# FLCOS_Projector_Driver.net
KiCad netlist of a schematic drawn in EAGLE
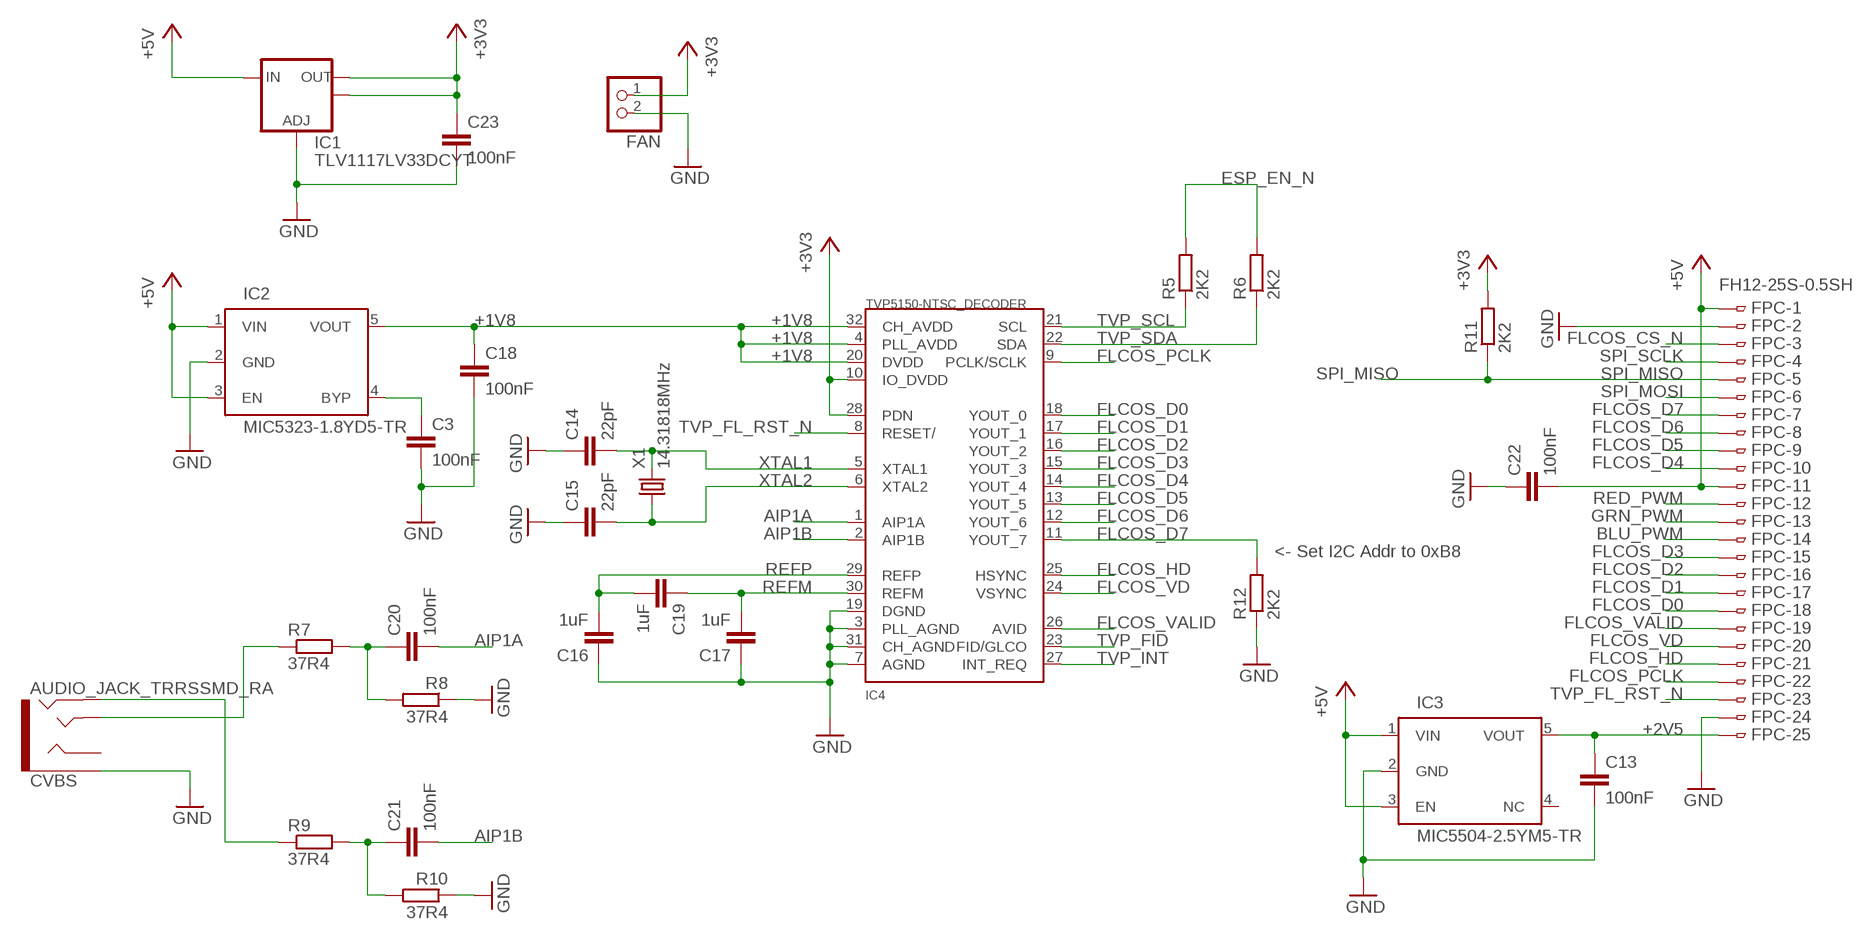
[diagram p0: schematic, sheet 1]
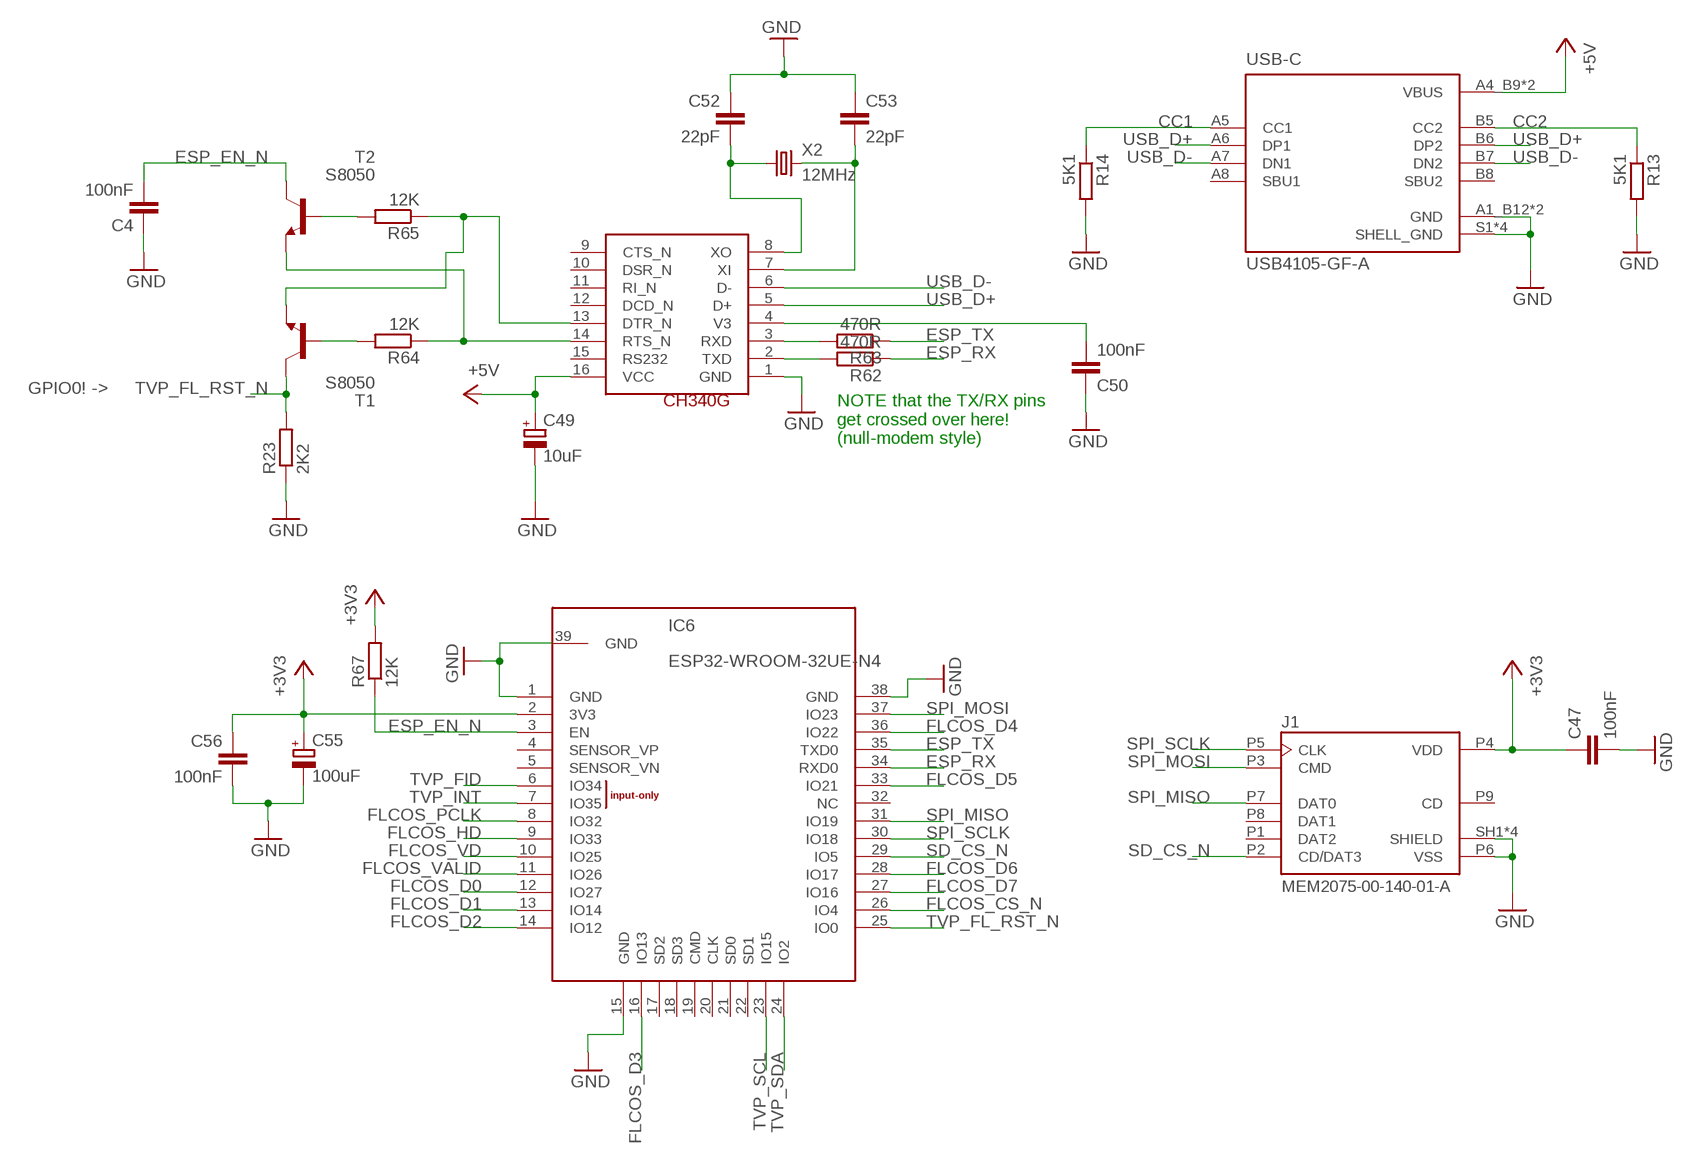
[diagram p1: schematic, sheet 2]
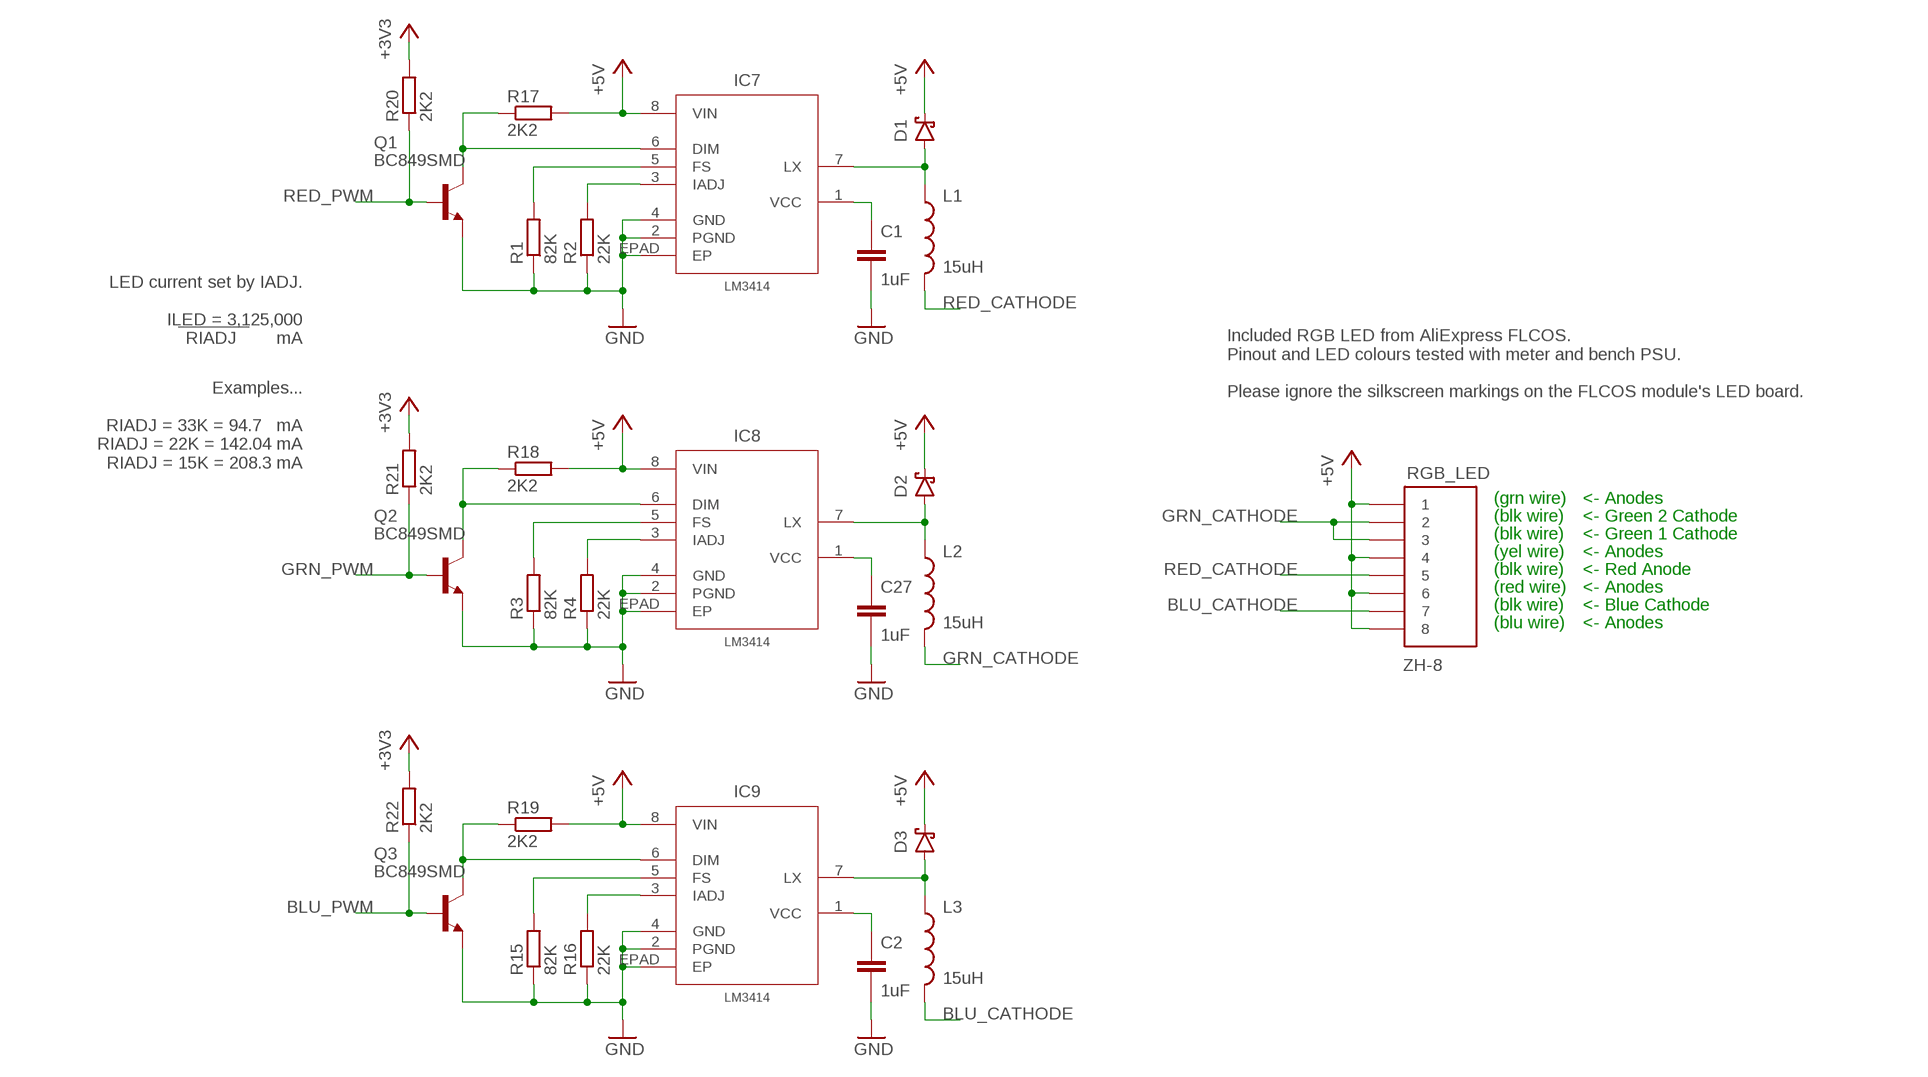
[diagram p2: schematic, sheet 3]

(export (version "E")
  (design (tool "Eeschema 10.0.6"))
  (components
    (comp (ref "C3")
      (value "100nF")
      (footprint "eagle-import:C0603")
      (libsource (lib "eagle-import") (part "C-EUC0603"))
    )
    (comp (ref "C13")
      (value "100nF")
      (footprint "eagle-import:C0603")
      (libsource (lib "eagle-import") (part "C-EUC0603"))
    )
    (comp (ref "C14")
      (value "22pF")
      (footprint "eagle-import:C0603")
      (libsource (lib "eagle-import") (part "C-EUC0603"))
    )
    (comp (ref "C15")
      (value "22pF")
      (footprint "eagle-import:C0603")
      (libsource (lib "eagle-import") (part "C-EUC0603"))
    )
    (comp (ref "C16")
      (value "1uF")
      (footprint "eagle-import:C0603")
      (libsource (lib "eagle-import") (part "C-EUC0603"))
    )
    (comp (ref "C17")
      (value "1uF")
      (footprint "eagle-import:C0603")
      (libsource (lib "eagle-import") (part "C-EUC0603"))
    )
    (comp (ref "C18")
      (value "100nF")
      (footprint "eagle-import:C0603")
      (libsource (lib "eagle-import") (part "C-EUC0603"))
    )
    (comp (ref "C19")
      (value "1uF")
      (footprint "eagle-import:C0603")
      (libsource (lib "eagle-import") (part "C-EUC0603"))
    )
    (comp (ref "C20")
      (value "100nF")
      (footprint "eagle-import:C0603")
      (libsource (lib "eagle-import") (part "C-EUC0603"))
    )
    (comp (ref "C21")
      (value "100nF")
      (footprint "eagle-import:C0603")
      (libsource (lib "eagle-import") (part "C-EUC0603"))
    )
    (comp (ref "C22")
      (value "100nF")
      (footprint "eagle-import:C0603")
      (libsource (lib "eagle-import") (part "C-EUC0603"))
    )
    (comp (ref "C23")
      (value "100nF")
      (footprint "eagle-import:C0603")
      (libsource (lib "eagle-import") (part "C-EUC0603"))
    )
    (comp (ref "CVBS")
      (value "AUDIO_JACK_TRRSSMD_RA")
      (footprint "eagle-import:AUDIO_JACK_3.5MM_TRRS_SMD_RA")
      (libsource (lib "eagle-import") (part "AUDIO_JACK_TRRSSMD_RA"))
    )
    (comp (ref "FAN")
      (value "JST_2PIN-THM")
      (footprint "eagle-import:JST-PH-2-THM")
      (libsource (lib "eagle-import") (part "JST_2PIN-THM"))
    )
    (comp (ref "FPC")
      (value "FH12-25S-0.5SH")
      (footprint "eagle-import:FH12-25S-0.5SH")
      (libsource (lib "eagle-import") (part "FH12-25S-0.5SH"))
    )
    (comp (ref "IC1")
      (value "TLV1117LV33DCYT")
      (footprint "eagle-import:SOT223")
      (libsource (lib "eagle-import") (part "V_REG_LM1117SOT223"))
    )
    (comp (ref "IC2")
      (value "MIC5323-1.8YD5-TR")
      (footprint "eagle-import:SOT23-5")
      (libsource (lib "eagle-import") (part "MIC5323-1.8YD5-TR"))
    )
    (comp (ref "IC3")
      (value "MIC5504-2.5YM5-TR")
      (footprint "eagle-import:SOT23-5")
      (libsource (lib "eagle-import") (part "MIC5504-2.5YM5-TR"))
    )
    (comp (ref "IC4")
      (value "TVP5150-NTSC_DECODER")
      (footprint "eagle-import:TQFP32-5MM")
      (libsource (lib "eagle-import") (part "TVP5150-NTSC_DECODER"))
    )
    (comp (ref "R5")
      (value "2K2")
      (footprint "eagle-import:R0603")
      (libsource (lib "eagle-import") (part "R-EU_R0603"))
    )
    (comp (ref "R6")
      (value "2K2")
      (footprint "eagle-import:R0603")
      (libsource (lib "eagle-import") (part "R-EU_R0603"))
    )
    (comp (ref "R7")
      (value "37R4")
      (footprint "eagle-import:R0603")
      (libsource (lib "eagle-import") (part "R-EU_R0603"))
    )
    (comp (ref "R8")
      (value "37R4")
      (footprint "eagle-import:R0603")
      (libsource (lib "eagle-import") (part "R-EU_R0603"))
    )
    (comp (ref "R9")
      (value "37R4")
      (footprint "eagle-import:R0603")
      (libsource (lib "eagle-import") (part "R-EU_R0603"))
    )
    (comp (ref "R10")
      (value "37R4")
      (footprint "eagle-import:R0603")
      (libsource (lib "eagle-import") (part "R-EU_R0603"))
    )
    (comp (ref "R11")
      (value "2K2")
      (footprint "eagle-import:R0603")
      (libsource (lib "eagle-import") (part "R-EU_R0603"))
    )
    (comp (ref "R12")
      (value "2K2")
      (footprint "eagle-import:R0603")
      (libsource (lib "eagle-import") (part "R-EU_R0603"))
    )
    (comp (ref "X1")
      (value "14.31818MHz")
      (footprint "eagle-import:CTS406")
      (libsource (lib "eagle-import") (part "CRYSTALCTS406"))
    )
    (comp (ref "C1")
      (value "1uF")
      (footprint "eagle-import:C0603")
      (libsource (lib "eagle-import") (part "CAPACITOR-CERAMICC0603"))
    )
    (comp (ref "C2")
      (value "1uF")
      (footprint "eagle-import:C0603")
      (libsource (lib "eagle-import") (part "CAPACITOR-CERAMICC0603"))
    )
    (comp (ref "C27")
      (value "1uF")
      (footprint "eagle-import:C0603")
      (libsource (lib "eagle-import") (part "CAPACITOR-CERAMICC0603"))
    )
    (comp (ref "D1")
      (value "\"SB34AFC-AU_R1_000A1 SB34AFC-AU_R1_000A1\"")
      (footprint "eagle-import:SMA-DIODE-SCHOTTKY")
      (libsource (lib "eagle-import") (part "DIODE-SCHOTTKYSMA"))
    )
    (comp (ref "D2")
      (value "\"SB34AFC-AU_R1_000A1 SB34AFC-AU_R1_000A1\"")
      (footprint "eagle-import:SMA-DIODE-SCHOTTKY")
      (libsource (lib "eagle-import") (part "DIODE-SCHOTTKYSMA"))
    )
    (comp (ref "D3")
      (value "\"SB34AFC-AU_R1_000A1 SB34AFC-AU_R1_000A1\"")
      (footprint "eagle-import:SMA-DIODE-SCHOTTKY")
      (libsource (lib "eagle-import") (part "DIODE-SCHOTTKYSMA"))
    )
    (comp (ref "IC7")
      (value "LM3414")
      (footprint "eagle-import:SO08-PAD")
      (libsource (lib "eagle-import") (part "LM3414SO08-PAD"))
    )
    (comp (ref "IC8")
      (value "LM3414")
      (footprint "eagle-import:SO08-PAD")
      (libsource (lib "eagle-import") (part "LM3414SO08-PAD"))
    )
    (comp (ref "IC9")
      (value "LM3414")
      (footprint "eagle-import:SO08-PAD")
      (libsource (lib "eagle-import") (part "LM3414SO08-PAD"))
    )
    (comp (ref "L1")
      (value "15uH")
      (footprint "eagle-import:TAIYO-YUDEN-6X6X2.8")
      (libsource (lib "eagle-import") (part "INDUCTOR-TAIYO-YUDEN-6X2.8"))
    )
    (comp (ref "L2")
      (value "15uH")
      (footprint "eagle-import:TAIYO-YUDEN-6X6X2.8")
      (libsource (lib "eagle-import") (part "INDUCTOR-TAIYO-YUDEN-6X2.8"))
    )
    (comp (ref "L3")
      (value "15uH")
      (footprint "eagle-import:TAIYO-YUDEN-6X6X2.8")
      (libsource (lib "eagle-import") (part "INDUCTOR-TAIYO-YUDEN-6X2.8"))
    )
    (comp (ref "Q1")
      (value "BC849SMD")
      (footprint "eagle-import:SOT23-BEC")
      (libsource (lib "eagle-import") (part "BC849SMD"))
    )
    (comp (ref "Q2")
      (value "BC849SMD")
      (footprint "eagle-import:SOT23-BEC")
      (libsource (lib "eagle-import") (part "BC849SMD"))
    )
    (comp (ref "Q3")
      (value "BC849SMD")
      (footprint "eagle-import:SOT23-BEC")
      (libsource (lib "eagle-import") (part "BC849SMD"))
    )
    (comp (ref "R1")
      (value "82K")
      (footprint "eagle-import:R0603")
      (libsource (lib "eagle-import") (part "R-EU_R0603"))
    )
    (comp (ref "R2")
      (value "22K")
      (footprint "eagle-import:R0603")
      (libsource (lib "eagle-import") (part "R-EU_R0603"))
    )
    (comp (ref "R3")
      (value "82K")
      (footprint "eagle-import:R0603")
      (libsource (lib "eagle-import") (part "R-EU_R0603"))
    )
    (comp (ref "R4")
      (value "22K")
      (footprint "eagle-import:R0603")
      (libsource (lib "eagle-import") (part "R-EU_R0603"))
    )
    (comp (ref "R15")
      (value "82K")
      (footprint "eagle-import:R0603")
      (libsource (lib "eagle-import") (part "R-EU_R0603"))
    )
    (comp (ref "R16")
      (value "22K")
      (footprint "eagle-import:R0603")
      (libsource (lib "eagle-import") (part "R-EU_R0603"))
    )
    (comp (ref "R17")
      (value "2K2")
      (footprint "eagle-import:R0603")
      (libsource (lib "eagle-import") (part "R-EU_R0603"))
    )
    (comp (ref "R18")
      (value "2K2")
      (footprint "eagle-import:R0603")
      (libsource (lib "eagle-import") (part "R-EU_R0603"))
    )
    (comp (ref "R19")
      (value "2K2")
      (footprint "eagle-import:R0603")
      (libsource (lib "eagle-import") (part "R-EU_R0603"))
    )
    (comp (ref "R20")
      (value "2K2")
      (footprint "eagle-import:R0603")
      (libsource (lib "eagle-import") (part "R-EU_R0603"))
    )
    (comp (ref "R21")
      (value "2K2")
      (footprint "eagle-import:R0603")
      (libsource (lib "eagle-import") (part "R-EU_R0603"))
    )
    (comp (ref "R22")
      (value "2K2")
      (footprint "eagle-import:R0603")
      (libsource (lib "eagle-import") (part "R-EU_R0603"))
    )
    (comp (ref "RGB_LED")
      (value "ZH-8")
      (footprint "eagle-import:ZH-8")
      (libsource (lib "eagle-import") (part "ZH-8"))
    )
    (comp (ref "C4")
      (value "100nF")
      (footprint "eagle-import:C0603")
      (libsource (lib "eagle-import") (part "C-EUC0603"))
    )
    (comp (ref "C47")
      (value "100nF")
      (footprint "eagle-import:C0603")
      (libsource (lib "eagle-import") (part "C-EUC0603"))
    )
    (comp (ref "C49")
      (value "10uF")
      (footprint "eagle-import:B_3528-21W")
      (libsource (lib "eagle-import") (part "CPOL-EUB/3528-21W"))
    )
    (comp (ref "C50")
      (value "100nF")
      (footprint "eagle-import:C0603")
      (libsource (lib "eagle-import") (part "C-EUC0603"))
    )
    (comp (ref "C52")
      (value "22pF")
      (footprint "eagle-import:C0603")
      (libsource (lib "eagle-import") (part "C-EUC0603"))
    )
    (comp (ref "C53")
      (value "22pF")
      (footprint "eagle-import:C0603")
      (libsource (lib "eagle-import") (part "C-EUC0603"))
    )
    (comp (ref "C55")
      (value "100uF")
      (footprint "eagle-import:C_6032-28R")
      (libsource (lib "eagle-import") (part "CPOL-EUC/6032-28R"))
    )
    (comp (ref "C56")
      (value "100nF")
      (footprint "eagle-import:C0603")
      (libsource (lib "eagle-import") (part "C-EUC0603"))
    )
    (comp (ref "IC5")
      (value "CH340G")
      (footprint "eagle-import:SOIC16")
      (libsource (lib "eagle-import") (part "CH340G"))
    )
    (comp (ref "IC6")
      (value "ESP32-WROOM-32UE-N4")
      (footprint "eagle-import:ESP32WROOM32D")
      (fields
        (field (name "MANUFACTURER_PART_NUMBER") "ESP32-WROOM-32U")
        (field (name "MOUSER_PART_NUMBER") "356-ESP32-WROOM-32U")
      )
      (libsource (lib "eagle-import") (part "ESP32-WROOM-32U"))
    )
    (comp (ref "J1")
      (value "MEM2075-00-140-01-A")
      (footprint "eagle-import:GCT_MEM2075-00-140-01-A")
      (fields (field (name "MF") "Global Connector Technology"))
      (libsource (lib "eagle-import") (part "MEM2075-00-140-01-A"))
    )
    (comp (ref "R13")
      (value "5K1")
      (footprint "eagle-import:R0603")
      (libsource (lib "eagle-import") (part "R-EU_R0603"))
    )
    (comp (ref "R14")
      (value "5K1")
      (footprint "eagle-import:R0603")
      (libsource (lib "eagle-import") (part "R-EU_R0603"))
    )
    (comp (ref "R23")
      (value "2K2")
      (footprint "eagle-import:R0603")
      (libsource (lib "eagle-import") (part "R-EU_R0603"))
    )
    (comp (ref "R62")
      (value "470R")
      (footprint "eagle-import:R0603")
      (libsource (lib "eagle-import") (part "R-EU_R0603"))
    )
    (comp (ref "R63")
      (value "470R")
      (footprint "eagle-import:R0603")
      (libsource (lib "eagle-import") (part "R-EU_R0603"))
    )
    (comp (ref "R64")
      (value "12K")
      (footprint "eagle-import:R0603")
      (libsource (lib "eagle-import") (part "R-EU_R0603"))
    )
    (comp (ref "R65")
      (value "12K")
      (footprint "eagle-import:R0603")
      (libsource (lib "eagle-import") (part "R-EU_R0603"))
    )
    (comp (ref "R67")
      (value "12K")
      (footprint "eagle-import:R0603")
      (libsource (lib "eagle-import") (part "R-EU_R0603"))
    )
    (comp (ref "T1")
      (value "S8050")
      (footprint "eagle-import:SOT23-BEC")
      (libsource (lib "eagle-import") (part "BC849SMD"))
    )
    (comp (ref "T2")
      (value "S8050")
      (footprint "eagle-import:SOT23-BEC")
      (libsource (lib "eagle-import") (part "BC849SMD"))
    )
    (comp (ref "USB-C")
      (value "USB4105-GF-A")
      (footprint "eagle-import:GCT_USB4105-GF-A")
      (fields (field (name "MF") "GCT"))
      (libsource (lib "eagle-import") (part "USB4105-GF-A"))
    )
    (comp (ref "X2")
      (value "12MHz")
      (footprint "eagle-import:CTS406")
      (libsource (lib "eagle-import") (part "CRYSTALCTS406"))
    )
  )
  (nets
    (net (code "1") (name "+1V8") (class "Default")
      (node (ref "C18") (pin "1") (pinfunction "1_1") (pintype "passive"))
      (node (ref "IC2") (pin "5") (pinfunction "VOUT_5") (pintype "power_in"))
      (node (ref "IC4") (pin "20") (pinfunction "DVDD_20") (pintype "bidirectional"))
      (node (ref "IC4") (pin "32") (pinfunction "CH_AVDD_32") (pintype "bidirectional"))
      (node (ref "IC4") (pin "4") (pinfunction "PLL_AVDD_4") (pintype "bidirectional"))
    )
    (net (code "2") (name "+2V5") (class "Default")
      (node (ref "C13") (pin "1") (pinfunction "1_1") (pintype "passive"))
      (node (ref "FPC") (pin "25") (pinfunction "1_25") (pintype "passive"))
      (node (ref "IC3") (pin "5") (pinfunction "VOUT_5") (pintype "power_in"))
    )
    (net (code "3") (name "+3V3") (class "Default")
      (node (ref "C23") (pin "1") (pinfunction "1_1") (pintype "passive"))
      (node (ref "C47") (pin "1") (pinfunction "1_1") (pintype "passive"))
      (node (ref "C55") (pin "+") (pinfunction "+_+") (pintype "passive"))
      (node (ref "C56") (pin "1") (pinfunction "1_1") (pintype "passive"))
      (node (ref "FAN") (pin "1") (pinfunction "2_1") (pintype "passive"))
      (node (ref "IC1") (pin "2") (pinfunction "OUT_2") (pintype "output"))
      (node (ref "IC1") (pin "4") (pinfunction "OUT_4") (pintype "output"))
      (node (ref "IC4") (pin "10") (pinfunction "IO_DVDD_10") (pintype "bidirectional"))
      (node (ref "IC4") (pin "28") (pinfunction "PDN_28") (pintype "bidirectional"))
      (node (ref "IC6") (pin "2") (pinfunction "3V3_2") (pintype "bidirectional"))
      (node (ref "J1") (pin "P4") (pinfunction "VDD_P4") (pintype "power_in"))
      (node (ref "R11") (pin "2") (pinfunction "2_2") (pintype "passive"))
      (node (ref "R20") (pin "2") (pinfunction "2_2") (pintype "passive"))
      (node (ref "R21") (pin "2") (pinfunction "2_2") (pintype "passive"))
      (node (ref "R22") (pin "2") (pinfunction "2_2") (pintype "passive"))
      (node (ref "R67") (pin "2") (pinfunction "2_2") (pintype "passive"))
    )
    (net (code "4") (name "+5V") (class "Default")
      (node (ref "C22") (pin "2") (pinfunction "2_2") (pintype "passive"))
      (node (ref "C49") (pin "+") (pinfunction "+_+") (pintype "passive"))
      (node (ref "D1") (pin "C") (pinfunction "C_C") (pintype "passive"))
      (node (ref "D2") (pin "C") (pinfunction "C_C") (pintype "passive"))
      (node (ref "D3") (pin "C") (pinfunction "C_C") (pintype "passive"))
      (node (ref "FPC") (pin "1") (pinfunction "1_1") (pintype "passive"))
      (node (ref "FPC") (pin "11") (pinfunction "1_11") (pintype "passive"))
      (node (ref "IC1") (pin "3") (pinfunction "IN_3") (pintype "input"))
      (node (ref "IC2") (pin "1") (pinfunction "VIN_1") (pintype "input"))
      (node (ref "IC2") (pin "3") (pinfunction "EN_3") (pintype "input"))
      (node (ref "IC3") (pin "1") (pinfunction "VIN_1") (pintype "input"))
      (node (ref "IC3") (pin "3") (pinfunction "EN_3") (pintype "input"))
      (node (ref "IC5") (pin "16") (pinfunction "VCC_16") (pintype "bidirectional"))
      (node (ref "IC7") (pin "8") (pinfunction "VIN_8") (pintype "bidirectional"))
      (node (ref "IC8") (pin "8") (pinfunction "VIN_8") (pintype "bidirectional"))
      (node (ref "IC9") (pin "8") (pinfunction "VIN_8") (pintype "bidirectional"))
      (node (ref "R17") (pin "2") (pinfunction "2_2") (pintype "passive"))
      (node (ref "R18") (pin "2") (pinfunction "2_2") (pintype "passive"))
      (node (ref "R19") (pin "2") (pinfunction "2_2") (pintype "passive"))
      (node (ref "RGB_LED") (pin "1") (pinfunction "1_1") (pintype "passive"))
      (node (ref "RGB_LED") (pin "4") (pinfunction "4_4") (pintype "passive"))
      (node (ref "RGB_LED") (pin "6") (pinfunction "6_6") (pintype "passive"))
      (node (ref "RGB_LED") (pin "8") (pinfunction "8_8") (pintype "passive"))
      (node (ref "USB-C") (pin "A4_B9") (pinfunction "VBUS_A4_B9") (pintype "power_in"))
      (node (ref "USB-C") (pin "B4_A9") (pinfunction "VBUS_B4_A9") (pintype "power_in"))
    )
    (net (code "5") (name "AIP1A") (class "Default")
      (node (ref "C20") (pin "2") (pinfunction "2_2") (pintype "passive"))
      (node (ref "IC4") (pin "1") (pinfunction "AIP1A_1") (pintype "bidirectional"))
    )
    (net (code "6") (name "AIP1B") (class "Default")
      (node (ref "C21") (pin "2") (pinfunction "2_2") (pintype "passive"))
      (node (ref "IC4") (pin "2") (pinfunction "AIP1B_2") (pintype "bidirectional"))
    )
    (net (code "7") (name "BLU_CATHODE") (class "Default")
      (node (ref "L3") (pin "2") (pinfunction "2_2") (pintype "passive"))
      (node (ref "RGB_LED") (pin "7") (pinfunction "7_7") (pintype "passive"))
    )
    (net (code "8") (name "BLU_PWM") (class "Default")
      (node (ref "FPC") (pin "14") (pinfunction "1_14") (pintype "passive"))
      (node (ref "Q3") (pin "B") (pinfunction "B_B") (pintype "passive"))
      (node (ref "R22") (pin "1") (pinfunction "1_1") (pintype "passive"))
    )
    (net (code "9") (name "CC1") (class "Default")
      (node (ref "R14") (pin "1") (pinfunction "1_1") (pintype "passive"))
      (node (ref "USB-C") (pin "A5") (pinfunction "CC1_A5") (pintype "bidirectional"))
    )
    (net (code "10") (name "CC2") (class "Default")
      (node (ref "R13") (pin "1") (pinfunction "1_1") (pintype "passive"))
      (node (ref "USB-C") (pin "B5") (pinfunction "CC2_B5") (pintype "bidirectional"))
    )
    (net (code "11") (name "ESP_EN_N") (class "Default")
      (node (ref "C4") (pin "2") (pinfunction "2_2") (pintype "passive"))
      (node (ref "IC6") (pin "3") (pinfunction "EN_3") (pintype "bidirectional"))
      (node (ref "R5") (pin "2") (pinfunction "2_2") (pintype "passive"))
      (node (ref "R6") (pin "2") (pinfunction "2_2") (pintype "passive"))
      (node (ref "R67") (pin "1") (pinfunction "1_1") (pintype "passive"))
      (node (ref "T2") (pin "C") (pinfunction "C_C") (pintype "passive"))
    )
    (net (code "12") (name "ESP_RX") (class "Default")
      (node (ref "IC6") (pin "34") (pinfunction "RXD0_34") (pintype "bidirectional"))
      (node (ref "R62") (pin "1") (pinfunction "1_1") (pintype "passive"))
    )
    (net (code "13") (name "ESP_TX") (class "Default")
      (node (ref "IC6") (pin "35") (pinfunction "TXD0_35") (pintype "bidirectional"))
      (node (ref "R63") (pin "1") (pinfunction "1_1") (pintype "passive"))
    )
    (net (code "14") (name "FLCOS_CS_N") (class "Default")
      (node (ref "FPC") (pin "3") (pinfunction "1_3") (pintype "passive"))
      (node (ref "IC6") (pin "26") (pinfunction "IO4_26") (pintype "bidirectional"))
    )
    (net (code "15") (name "FLCOS_D0") (class "Default")
      (node (ref "FPC") (pin "18") (pinfunction "1_18") (pintype "passive"))
      (node (ref "IC4") (pin "18") (pinfunction "YOUT_0_18") (pintype "bidirectional"))
      (node (ref "IC6") (pin "12") (pinfunction "IO27_12") (pintype "bidirectional"))
    )
    (net (code "16") (name "FLCOS_D1") (class "Default")
      (node (ref "FPC") (pin "17") (pinfunction "1_17") (pintype "passive"))
      (node (ref "IC4") (pin "17") (pinfunction "YOUT_1_17") (pintype "bidirectional"))
      (node (ref "IC6") (pin "13") (pinfunction "IO14_13") (pintype "bidirectional"))
    )
    (net (code "17") (name "FLCOS_D2") (class "Default")
      (node (ref "FPC") (pin "16") (pinfunction "1_16") (pintype "passive"))
      (node (ref "IC4") (pin "16") (pinfunction "YOUT_2_16") (pintype "bidirectional"))
      (node (ref "IC6") (pin "14") (pinfunction "IO12_14") (pintype "bidirectional"))
    )
    (net (code "18") (name "FLCOS_D3") (class "Default")
      (node (ref "FPC") (pin "15") (pinfunction "1_15") (pintype "passive"))
      (node (ref "IC4") (pin "15") (pinfunction "YOUT_3_15") (pintype "bidirectional"))
      (node (ref "IC6") (pin "16") (pinfunction "IO13_16") (pintype "bidirectional"))
    )
    (net (code "19") (name "FLCOS_D4") (class "Default")
      (node (ref "FPC") (pin "10") (pinfunction "1_10") (pintype "passive"))
      (node (ref "IC4") (pin "14") (pinfunction "YOUT_4_14") (pintype "bidirectional"))
      (node (ref "IC6") (pin "36") (pinfunction "IO22_36") (pintype "bidirectional"))
    )
    (net (code "20") (name "FLCOS_D5") (class "Default")
      (node (ref "FPC") (pin "9") (pinfunction "1_9") (pintype "passive"))
      (node (ref "IC4") (pin "13") (pinfunction "YOUT_5_13") (pintype "bidirectional"))
      (node (ref "IC6") (pin "33") (pinfunction "IO21_33") (pintype "bidirectional"))
    )
    (net (code "21") (name "FLCOS_D6") (class "Default")
      (node (ref "FPC") (pin "8") (pinfunction "1_8") (pintype "passive"))
      (node (ref "IC4") (pin "12") (pinfunction "YOUT_6_12") (pintype "bidirectional"))
      (node (ref "IC6") (pin "28") (pinfunction "IO17_28") (pintype "bidirectional"))
    )
    (net (code "22") (name "FLCOS_D7") (class "Default")
      (node (ref "FPC") (pin "7") (pinfunction "1_7") (pintype "passive"))
      (node (ref "IC4") (pin "11") (pinfunction "YOUT_7_11") (pintype "bidirectional"))
      (node (ref "IC6") (pin "27") (pinfunction "IO16_27") (pintype "bidirectional"))
      (node (ref "R12") (pin "2") (pinfunction "2_2") (pintype "passive"))
    )
    (net (code "23") (name "FLCOS_HD") (class "Default")
      (node (ref "FPC") (pin "21") (pinfunction "1_21") (pintype "passive"))
      (node (ref "IC4") (pin "25") (pinfunction "HSYNC_25") (pintype "bidirectional"))
      (node (ref "IC6") (pin "9") (pinfunction "IO33_9") (pintype "bidirectional"))
    )
    (net (code "24") (name "FLCOS_PCLK") (class "Default")
      (node (ref "FPC") (pin "22") (pinfunction "1_22") (pintype "passive"))
      (node (ref "IC4") (pin "9") (pinfunction "PCLK/SCLK_9") (pintype "bidirectional"))
      (node (ref "IC6") (pin "8") (pinfunction "IO32_8") (pintype "bidirectional"))
    )
    (net (code "25") (name "FLCOS_VALID") (class "Default")
      (node (ref "FPC") (pin "19") (pinfunction "1_19") (pintype "passive"))
      (node (ref "IC4") (pin "26") (pinfunction "AVID_26") (pintype "bidirectional"))
      (node (ref "IC6") (pin "11") (pinfunction "IO26_11") (pintype "bidirectional"))
    )
    (net (code "26") (name "FLCOS_VD") (class "Default")
      (node (ref "FPC") (pin "20") (pinfunction "1_20") (pintype "passive"))
      (node (ref "IC4") (pin "24") (pinfunction "VSYNC_24") (pintype "bidirectional"))
      (node (ref "IC6") (pin "10") (pinfunction "IO25_10") (pintype "bidirectional"))
    )
    (net (code "27") (name "GND") (class "Default")
      (node (ref "C1") (pin "2") (pinfunction "2_2") (pintype "passive"))
      (node (ref "C13") (pin "2") (pinfunction "2_2") (pintype "passive"))
      (node (ref "C14") (pin "1") (pinfunction "1_1") (pintype "passive"))
      (node (ref "C15") (pin "1") (pinfunction "1_1") (pintype "passive"))
      (node (ref "C16") (pin "1") (pinfunction "1_1") (pintype "passive"))
      (node (ref "C17") (pin "1") (pinfunction "1_1") (pintype "passive"))
      (node (ref "C18") (pin "2") (pinfunction "2_2") (pintype "passive"))
      (node (ref "C2") (pin "2") (pinfunction "2_2") (pintype "passive"))
      (node (ref "C22") (pin "1") (pinfunction "1_1") (pintype "passive"))
      (node (ref "C23") (pin "2") (pinfunction "2_2") (pintype "passive"))
      (node (ref "C27") (pin "2") (pinfunction "2_2") (pintype "passive"))
      (node (ref "C3") (pin "2") (pinfunction "2_2") (pintype "passive"))
      (node (ref "C4") (pin "1") (pinfunction "1_1") (pintype "passive"))
      (node (ref "C47") (pin "2") (pinfunction "2_2") (pintype "passive"))
      (node (ref "C49") (pin "-") (pinfunction "-_-") (pintype "passive"))
      (node (ref "C50") (pin "1") (pinfunction "1_1") (pintype "passive"))
      (node (ref "C52") (pin "1") (pinfunction "1_1") (pintype "passive"))
      (node (ref "C53") (pin "1") (pinfunction "1_1") (pintype "passive"))
      (node (ref "C55") (pin "-") (pinfunction "-_-") (pintype "passive"))
      (node (ref "C56") (pin "2") (pinfunction "2_2") (pintype "passive"))
      (node (ref "CVBS") (pin "EARTH") (pinfunction "EARTH_EARTH") (pintype "bidirectional"))
      (node (ref "FAN") (pin "2") (pinfunction "1_2") (pintype "passive"))
      (node (ref "FPC") (pin "2") (pinfunction "1_2") (pintype "passive"))
      (node (ref "FPC") (pin "24") (pinfunction "1_24") (pintype "passive"))
      (node (ref "IC1") (pin "1") (pinfunction "ADJ_1") (pintype "input"))
      (node (ref "IC2") (pin "2") (pinfunction "GND_2") (pintype "power_in"))
      (node (ref "IC3") (pin "2") (pinfunction "GND_2") (pintype "power_in"))
      (node (ref "IC4") (pin "19") (pinfunction "DGND_19") (pintype "bidirectional"))
      (node (ref "IC4") (pin "3") (pinfunction "PLL_AGND_3") (pintype "bidirectional"))
      (node (ref "IC4") (pin "31") (pinfunction "CH_AGND_31") (pintype "bidirectional"))
      (node (ref "IC4") (pin "7") (pinfunction "AGND_7") (pintype "bidirectional"))
      (node (ref "IC5") (pin "1") (pinfunction "GND_1") (pintype "bidirectional"))
      (node (ref "IC6") (pin "1") (pinfunction "GND_1") (pintype "bidirectional"))
      (node (ref "IC6") (pin "15") (pinfunction "GND_15") (pintype "bidirectional"))
      (node (ref "IC6") (pin "38") (pinfunction "GND_38") (pintype "bidirectional"))
      (node (ref "IC6") (pin "39") (pinfunction "GND_39") (pintype "bidirectional"))
      (node (ref "IC7") (pin "2") (pinfunction "PGND_2") (pintype "bidirectional"))
      (node (ref "IC7") (pin "4") (pinfunction "GND_4") (pintype "bidirectional"))
      (node (ref "IC7") (pin "EPAD") (pinfunction "EP_EPAD") (pintype "bidirectional"))
      (node (ref "IC8") (pin "2") (pinfunction "PGND_2") (pintype "bidirectional"))
      (node (ref "IC8") (pin "4") (pinfunction "GND_4") (pintype "bidirectional"))
      (node (ref "IC8") (pin "EPAD") (pinfunction "EP_EPAD") (pintype "bidirectional"))
      (node (ref "IC9") (pin "2") (pinfunction "PGND_2") (pintype "bidirectional"))
      (node (ref "IC9") (pin "4") (pinfunction "GND_4") (pintype "bidirectional"))
      (node (ref "IC9") (pin "EPAD") (pinfunction "EP_EPAD") (pintype "bidirectional"))
      (node (ref "J1") (pin "P6") (pinfunction "VSS_P6") (pintype "power_in"))
      (node (ref "J1") (pin "SH1") (pinfunction "SHIELD_SH1") (pintype "power_in"))
      (node (ref "J1") (pin "SH2") (pinfunction "SHIELD_SH2") (pintype "power_in"))
      (node (ref "J1") (pin "SH3") (pinfunction "SHIELD_SH3") (pintype "power_in"))
      (node (ref "J1") (pin "SH4") (pinfunction "SHIELD_SH4") (pintype "power_in"))
      (node (ref "Q1") (pin "E") (pinfunction "E_E") (pintype "passive"))
      (node (ref "Q2") (pin "E") (pinfunction "E_E") (pintype "passive"))
      (node (ref "Q3") (pin "E") (pinfunction "E_E") (pintype "passive"))
      (node (ref "R1") (pin "1") (pinfunction "1_1") (pintype "passive"))
      (node (ref "R10") (pin "1") (pinfunction "1_1") (pintype "passive"))
      (node (ref "R12") (pin "1") (pinfunction "1_1") (pintype "passive"))
      (node (ref "R13") (pin "2") (pinfunction "2_2") (pintype "passive"))
      (node (ref "R14") (pin "2") (pinfunction "2_2") (pintype "passive"))
      (node (ref "R15") (pin "1") (pinfunction "1_1") (pintype "passive"))
      (node (ref "R16") (pin "1") (pinfunction "1_1") (pintype "passive"))
      (node (ref "R2") (pin "1") (pinfunction "1_1") (pintype "passive"))
      (node (ref "R23") (pin "1") (pinfunction "1_1") (pintype "passive"))
      (node (ref "R3") (pin "1") (pinfunction "1_1") (pintype "passive"))
      (node (ref "R4") (pin "1") (pinfunction "1_1") (pintype "passive"))
      (node (ref "R8") (pin "1") (pinfunction "1_1") (pintype "passive"))
      (node (ref "USB-C") (pin "A1_B12") (pinfunction "GND_A1_B12") (pintype "power_in"))
      (node (ref "USB-C") (pin "B1_A12") (pinfunction "GND_B1_A12") (pintype "power_in"))
      (node (ref "USB-C") (pin "S1") (pinfunction "SHELL_GND_S1") (pintype "power_in"))
      (node (ref "USB-C") (pin "S2") (pinfunction "SHELL_GND_S2") (pintype "power_in"))
      (node (ref "USB-C") (pin "S3") (pinfunction "SHELL_GND_S3") (pintype "power_in"))
      (node (ref "USB-C") (pin "S4") (pinfunction "SHELL_GND_S4") (pintype "power_in"))
    )
    (net (code "28") (name "GRN_CATHODE") (class "Default")
      (node (ref "L2") (pin "2") (pinfunction "2_2") (pintype "passive"))
      (node (ref "RGB_LED") (pin "2") (pinfunction "2_2") (pintype "passive"))
      (node (ref "RGB_LED") (pin "3") (pinfunction "3_3") (pintype "passive"))
    )
    (net (code "29") (name "GRN_PWM") (class "Default")
      (node (ref "FPC") (pin "13") (pinfunction "1_13") (pintype "passive"))
      (node (ref "Q2") (pin "B") (pinfunction "B_B") (pintype "passive"))
      (node (ref "R21") (pin "1") (pinfunction "1_1") (pintype "passive"))
    )
    (net (code "30") (name "Net-(C20-Pad1)") (class "Default")
      (node (ref "C20") (pin "1") (pinfunction "1_1") (pintype "passive"))
      (node (ref "R7") (pin "2") (pinfunction "2_2") (pintype "passive"))
      (node (ref "R8") (pin "2") (pinfunction "2_2") (pintype "passive"))
    )
    (net (code "31") (name "Net-(C21-Pad1)") (class "Default")
      (node (ref "C21") (pin "1") (pinfunction "1_1") (pintype "passive"))
      (node (ref "R10") (pin "2") (pinfunction "2_2") (pintype "passive"))
      (node (ref "R9") (pin "2") (pinfunction "2_2") (pintype "passive"))
    )
    (net (code "32") (name "Net-(CVBS-PadRING2)") (class "Default")
      (node (ref "CVBS") (pin "RING2") (pinfunction "RING2_RING2") (pintype "bidirectional"))
      (node (ref "R9") (pin "1") (pinfunction "1_1") (pintype "passive"))
    )
    (net (code "33") (name "Net-(CVBS-PadTIP)") (class "Default")
      (node (ref "CVBS") (pin "TIP") (pinfunction "TIP_TIP") (pintype "bidirectional"))
      (node (ref "R7") (pin "1") (pinfunction "1_1") (pintype "passive"))
    )
    (net (code "34") (name "Net-(IC2-BYP)") (class "Default")
      (node (ref "C3") (pin "1") (pinfunction "1_1") (pintype "passive"))
      (node (ref "IC2") (pin "4") (pinfunction "BYP_4") (pintype "bidirectional"))
    )
    (net (code "35") (name "Net-(IC5-DTR_N)") (class "Default")
      (node (ref "IC5") (pin "13") (pinfunction "DTR_N_13") (pintype "bidirectional"))
      (node (ref "R65") (pin "1") (pinfunction "1_1") (pintype "passive"))
      (node (ref "T1") (pin "E") (pinfunction "E_E") (pintype "passive"))
    )
    (net (code "36") (name "Net-(IC5-RTS_N)") (class "Default")
      (node (ref "IC5") (pin "14") (pinfunction "RTS_N_14") (pintype "bidirectional"))
      (node (ref "R64") (pin "1") (pinfunction "1_1") (pintype "passive"))
      (node (ref "T2") (pin "E") (pinfunction "E_E") (pintype "passive"))
    )
    (net (code "37") (name "Net-(IC5-RXD)") (class "Default")
      (node (ref "IC5") (pin "3") (pinfunction "RXD_3") (pintype "bidirectional"))
      (node (ref "R63") (pin "2") (pinfunction "2_2") (pintype "passive"))
    )
    (net (code "38") (name "Net-(IC5-TXD)") (class "Default")
      (node (ref "IC5") (pin "2") (pinfunction "TXD_2") (pintype "bidirectional"))
      (node (ref "R62") (pin "2") (pinfunction "2_2") (pintype "passive"))
    )
    (net (code "39") (name "Net-(IC5-V3)") (class "Default")
      (node (ref "C50") (pin "2") (pinfunction "2_2") (pintype "passive"))
      (node (ref "IC5") (pin "4") (pinfunction "V3_4") (pintype "bidirectional"))
    )
    (net (code "40") (name "Net-(IC5-XI)") (class "Default")
      (node (ref "C53") (pin "2") (pinfunction "2_2") (pintype "passive"))
      (node (ref "IC5") (pin "7") (pinfunction "XI_7") (pintype "bidirectional"))
      (node (ref "X2") (pin "3") (pinfunction "2_3") (pintype "passive"))
    )
    (net (code "41") (name "Net-(IC5-XO)") (class "Default")
      (node (ref "C52") (pin "2") (pinfunction "2_2") (pintype "passive"))
      (node (ref "IC5") (pin "8") (pinfunction "XO_8") (pintype "bidirectional"))
      (node (ref "X2") (pin "1") (pinfunction "1_1") (pintype "passive"))
    )
    (net (code "42") (name "Net-(IC7-DIM)") (class "Default")
      (node (ref "IC7") (pin "6") (pinfunction "DIM_6") (pintype "bidirectional"))
      (node (ref "Q1") (pin "C") (pinfunction "C_C") (pintype "passive"))
      (node (ref "R17") (pin "1") (pinfunction "1_1") (pintype "passive"))
    )
    (net (code "43") (name "Net-(IC7-FS)") (class "Default")
      (node (ref "IC7") (pin "5") (pinfunction "FS_5") (pintype "bidirectional"))
      (node (ref "R1") (pin "2") (pinfunction "2_2") (pintype "passive"))
    )
    (net (code "44") (name "Net-(IC7-IADJ)") (class "Default")
      (node (ref "IC7") (pin "3") (pinfunction "IADJ_3") (pintype "bidirectional"))
      (node (ref "R2") (pin "2") (pinfunction "2_2") (pintype "passive"))
    )
    (net (code "45") (name "Net-(IC7-LX)") (class "Default")
      (node (ref "D1") (pin "A") (pinfunction "A_A") (pintype "passive"))
      (node (ref "IC7") (pin "7") (pinfunction "LX_7") (pintype "bidirectional"))
      (node (ref "L1") (pin "1") (pinfunction "1_1") (pintype "passive"))
    )
    (net (code "46") (name "Net-(IC7-VCC)") (class "Default")
      (node (ref "C1") (pin "1") (pinfunction "1_1") (pintype "passive"))
      (node (ref "IC7") (pin "1") (pinfunction "VCC_1") (pintype "bidirectional"))
    )
    (net (code "47") (name "Net-(IC8-DIM)") (class "Default")
      (node (ref "IC8") (pin "6") (pinfunction "DIM_6") (pintype "bidirectional"))
      (node (ref "Q2") (pin "C") (pinfunction "C_C") (pintype "passive"))
      (node (ref "R18") (pin "1") (pinfunction "1_1") (pintype "passive"))
    )
    (net (code "48") (name "Net-(IC8-FS)") (class "Default")
      (node (ref "IC8") (pin "5") (pinfunction "FS_5") (pintype "bidirectional"))
      (node (ref "R3") (pin "2") (pinfunction "2_2") (pintype "passive"))
    )
    (net (code "49") (name "Net-(IC8-IADJ)") (class "Default")
      (node (ref "IC8") (pin "3") (pinfunction "IADJ_3") (pintype "bidirectional"))
      (node (ref "R4") (pin "2") (pinfunction "2_2") (pintype "passive"))
    )
    (net (code "50") (name "Net-(IC8-LX)") (class "Default")
      (node (ref "D2") (pin "A") (pinfunction "A_A") (pintype "passive"))
      (node (ref "IC8") (pin "7") (pinfunction "LX_7") (pintype "bidirectional"))
      (node (ref "L2") (pin "1") (pinfunction "1_1") (pintype "passive"))
    )
    (net (code "51") (name "Net-(IC8-VCC)") (class "Default")
      (node (ref "C27") (pin "1") (pinfunction "1_1") (pintype "passive"))
      (node (ref "IC8") (pin "1") (pinfunction "VCC_1") (pintype "bidirectional"))
    )
    (net (code "52") (name "Net-(IC9-DIM)") (class "Default")
      (node (ref "IC9") (pin "6") (pinfunction "DIM_6") (pintype "bidirectional"))
      (node (ref "Q3") (pin "C") (pinfunction "C_C") (pintype "passive"))
      (node (ref "R19") (pin "1") (pinfunction "1_1") (pintype "passive"))
    )
    (net (code "53") (name "Net-(IC9-FS)") (class "Default")
      (node (ref "IC9") (pin "5") (pinfunction "FS_5") (pintype "bidirectional"))
      (node (ref "R15") (pin "2") (pinfunction "2_2") (pintype "passive"))
    )
    (net (code "54") (name "Net-(IC9-IADJ)") (class "Default")
      (node (ref "IC9") (pin "3") (pinfunction "IADJ_3") (pintype "bidirectional"))
      (node (ref "R16") (pin "2") (pinfunction "2_2") (pintype "passive"))
    )
    (net (code "55") (name "Net-(IC9-LX)") (class "Default")
      (node (ref "D3") (pin "A") (pinfunction "A_A") (pintype "passive"))
      (node (ref "IC9") (pin "7") (pinfunction "LX_7") (pintype "bidirectional"))
      (node (ref "L3") (pin "1") (pinfunction "1_1") (pintype "passive"))
    )
    (net (code "56") (name "Net-(IC9-VCC)") (class "Default")
      (node (ref "C2") (pin "1") (pinfunction "1_1") (pintype "passive"))
      (node (ref "IC9") (pin "1") (pinfunction "VCC_1") (pintype "bidirectional"))
    )
    (net (code "57") (name "Net-(R64-Pad2)") (class "Default")
      (node (ref "R64") (pin "2") (pinfunction "2_2") (pintype "passive"))
      (node (ref "T1") (pin "B") (pinfunction "B_B") (pintype "passive"))
    )
    (net (code "58") (name "Net-(R65-Pad2)") (class "Default")
      (node (ref "R65") (pin "2") (pinfunction "2_2") (pintype "passive"))
      (node (ref "T2") (pin "B") (pinfunction "B_B") (pintype "passive"))
    )
    (net (code "59") (name "RED_CATHODE") (class "Default")
      (node (ref "L1") (pin "2") (pinfunction "2_2") (pintype "passive"))
      (node (ref "RGB_LED") (pin "5") (pinfunction "5_5") (pintype "passive"))
    )
    (net (code "60") (name "RED_PWM") (class "Default")
      (node (ref "FPC") (pin "12") (pinfunction "1_12") (pintype "passive"))
      (node (ref "Q1") (pin "B") (pinfunction "B_B") (pintype "passive"))
      (node (ref "R20") (pin "1") (pinfunction "1_1") (pintype "passive"))
    )
    (net (code "61") (name "REFM") (class "Default")
      (node (ref "C17") (pin "2") (pinfunction "2_2") (pintype "passive"))
      (node (ref "C19") (pin "1") (pinfunction "1_1") (pintype "passive"))
      (node (ref "IC4") (pin "30") (pinfunction "REFM_30") (pintype "bidirectional"))
    )
    (net (code "62") (name "REFP") (class "Default")
      (node (ref "C16") (pin "2") (pinfunction "2_2") (pintype "passive"))
      (node (ref "C19") (pin "2") (pinfunction "2_2") (pintype "passive"))
      (node (ref "IC4") (pin "29") (pinfunction "REFP_29") (pintype "bidirectional"))
    )
    (net (code "63") (name "SD_CS_N") (class "Default")
      (node (ref "IC6") (pin "29") (pinfunction "IO5_29") (pintype "bidirectional"))
      (node (ref "J1") (pin "P2") (pinfunction "CD/DAT3_P2") (pintype "bidirectional"))
    )
    (net (code "64") (name "SPI_MISO") (class "Default")
      (node (ref "FPC") (pin "5") (pinfunction "1_5") (pintype "passive"))
      (node (ref "IC6") (pin "31") (pinfunction "IO19_31") (pintype "bidirectional"))
      (node (ref "J1") (pin "P7") (pinfunction "DAT0_P7") (pintype "bidirectional"))
      (node (ref "R11") (pin "1") (pinfunction "1_1") (pintype "passive"))
    )
    (net (code "65") (name "SPI_MOSI") (class "Default")
      (node (ref "FPC") (pin "6") (pinfunction "1_6") (pintype "passive"))
      (node (ref "IC6") (pin "37") (pinfunction "IO23_37") (pintype "bidirectional"))
      (node (ref "J1") (pin "P3") (pinfunction "CMD_P3") (pintype "bidirectional"))
    )
    (net (code "66") (name "SPI_SCLK") (class "Default")
      (node (ref "FPC") (pin "4") (pinfunction "1_4") (pintype "passive"))
      (node (ref "IC6") (pin "30") (pinfunction "IO18_30") (pintype "bidirectional"))
      (node (ref "J1") (pin "P5") (pinfunction "CLK_P5") (pintype "bidirectional"))
    )
    (net (code "67") (name "TVP_FID") (class "Default")
      (node (ref "IC4") (pin "23") (pinfunction "FID/GLCO_23") (pintype "bidirectional"))
      (node (ref "IC6") (pin "6") (pinfunction "IO34_6") (pintype "bidirectional"))
    )
    (net (code "68") (name "TVP_FL_RST_N") (class "Default")
      (node (ref "FPC") (pin "23") (pinfunction "1_23") (pintype "passive"))
      (node (ref "IC4") (pin "8") (pinfunction "RESET/_8") (pintype "bidirectional"))
      (node (ref "IC6") (pin "25") (pinfunction "IO0_25") (pintype "bidirectional"))
      (node (ref "R23") (pin "2") (pinfunction "2_2") (pintype "passive"))
      (node (ref "T1") (pin "C") (pinfunction "C_C") (pintype "passive"))
    )
    (net (code "69") (name "TVP_INT") (class "Default")
      (node (ref "IC4") (pin "27") (pinfunction "INT_REQ_27") (pintype "bidirectional"))
      (node (ref "IC6") (pin "7") (pinfunction "IO35_7") (pintype "bidirectional"))
    )
    (net (code "70") (name "TVP_SCL") (class "Default")
      (node (ref "IC4") (pin "21") (pinfunction "SCL_21") (pintype "bidirectional"))
      (node (ref "IC6") (pin "23") (pinfunction "IO15_23") (pintype "bidirectional"))
      (node (ref "R5") (pin "1") (pinfunction "1_1") (pintype "passive"))
    )
    (net (code "71") (name "TVP_SDA") (class "Default")
      (node (ref "IC4") (pin "22") (pinfunction "SDA_22") (pintype "bidirectional"))
      (node (ref "IC6") (pin "24") (pinfunction "IO2_24") (pintype "bidirectional"))
      (node (ref "R6") (pin "1") (pinfunction "1_1") (pintype "passive"))
    )
    (net (code "72") (name "USB_D+") (class "Default")
      (node (ref "IC5") (pin "5") (pinfunction "D+_5") (pintype "bidirectional"))
      (node (ref "USB-C") (pin "A6") (pinfunction "DP1_A6") (pintype "bidirectional"))
      (node (ref "USB-C") (pin "B6") (pinfunction "DP2_B6") (pintype "bidirectional"))
    )
    (net (code "73") (name "USB_D-") (class "Default")
      (node (ref "IC5") (pin "6") (pinfunction "D-_6") (pintype "bidirectional"))
      (node (ref "USB-C") (pin "A7") (pinfunction "DN1_A7") (pintype "bidirectional"))
      (node (ref "USB-C") (pin "B7") (pinfunction "DN2_B7") (pintype "bidirectional"))
    )
    (net (code "74") (name "XTAL1") (class "Default")
      (node (ref "C14") (pin "2") (pinfunction "2_2") (pintype "passive"))
      (node (ref "IC4") (pin "5") (pinfunction "XTAL1_5") (pintype "bidirectional"))
      (node (ref "X1") (pin "3") (pinfunction "2_3") (pintype "passive"))
    )
    (net (code "75") (name "XTAL2") (class "Default")
      (node (ref "C15") (pin "2") (pinfunction "2_2") (pintype "passive"))
      (node (ref "IC4") (pin "6") (pinfunction "XTAL2_6") (pintype "bidirectional"))
      (node (ref "X1") (pin "1") (pinfunction "1_1") (pintype "passive"))
    )
    (net (code "76") (name "unconnected-(CVBS-PadRING1)") (class "Default")
      (node (ref "CVBS") (pin "RING1") (pinfunction "RING1_RING1") (pintype "bidirectional"))
    )
    (net (code "77") (name "unconnected-(IC3-NC-Pad4)") (class "Default")
      (node (ref "IC3") (pin "4") (pinfunction "NC_4") (pintype "no_connect"))
    )
    (net (code "78") (name "unconnected-(IC5-CTS_N-Pad9)") (class "Default")
      (node (ref "IC5") (pin "9") (pinfunction "CTS_N_9") (pintype "bidirectional"))
    )
    (net (code "79") (name "unconnected-(IC5-DCD_N-Pad12)") (class "Default")
      (node (ref "IC5") (pin "12") (pinfunction "DCD_N_12") (pintype "bidirectional"))
    )
    (net (code "80") (name "unconnected-(IC5-DSR_N-Pad10)") (class "Default")
      (node (ref "IC5") (pin "10") (pinfunction "DSR_N_10") (pintype "bidirectional"))
    )
    (net (code "81") (name "unconnected-(IC5-RI_N-Pad11)") (class "Default")
      (node (ref "IC5") (pin "11") (pinfunction "RI_N_11") (pintype "bidirectional"))
    )
    (net (code "82") (name "unconnected-(IC5-RS232-Pad15)") (class "Default")
      (node (ref "IC5") (pin "15") (pinfunction "RS232_15") (pintype "bidirectional"))
    )
    (net (code "83") (name "unconnected-(IC6-CLK-Pad20)") (class "Default")
      (node (ref "IC6") (pin "20") (pinfunction "CLK_20") (pintype "bidirectional"))
    )
    (net (code "84") (name "unconnected-(IC6-CMD-Pad19)") (class "Default")
      (node (ref "IC6") (pin "19") (pinfunction "CMD_19") (pintype "bidirectional"))
    )
    (net (code "85") (name "unconnected-(IC6-NC-Pad32)") (class "Default")
      (node (ref "IC6") (pin "32") (pinfunction "NC_32") (pintype "no_connect"))
    )
    (net (code "86") (name "unconnected-(IC6-SD0-Pad21)") (class "Default")
      (node (ref "IC6") (pin "21") (pinfunction "SD0_21") (pintype "bidirectional"))
    )
    (net (code "87") (name "unconnected-(IC6-SD1-Pad22)") (class "Default")
      (node (ref "IC6") (pin "22") (pinfunction "SD1_22") (pintype "bidirectional"))
    )
    (net (code "88") (name "unconnected-(IC6-SD2-Pad17)") (class "Default")
      (node (ref "IC6") (pin "17") (pinfunction "SD2_17") (pintype "bidirectional"))
    )
    (net (code "89") (name "unconnected-(IC6-SD3-Pad18)") (class "Default")
      (node (ref "IC6") (pin "18") (pinfunction "SD3_18") (pintype "bidirectional"))
    )
    (net (code "90") (name "unconnected-(IC6-SENSOR_VN-Pad5)") (class "Default")
      (node (ref "IC6") (pin "5") (pinfunction "SENSOR_VN_5") (pintype "bidirectional"))
    )
    (net (code "91") (name "unconnected-(IC6-SENSOR_VP-Pad4)") (class "Default")
      (node (ref "IC6") (pin "4") (pinfunction "SENSOR_VP_4") (pintype "bidirectional"))
    )
    (net (code "92") (name "unconnected-(J1-CD-PadP9)") (class "Default")
      (node (ref "J1") (pin "P9") (pinfunction "CD_P9") (pintype "passive"))
    )
    (net (code "93") (name "unconnected-(J1-DAT1-PadP8)") (class "Default")
      (node (ref "J1") (pin "P8") (pinfunction "DAT1_P8") (pintype "bidirectional"))
    )
    (net (code "94") (name "unconnected-(J1-DAT2-PadP1)") (class "Default")
      (node (ref "J1") (pin "P1") (pinfunction "DAT2_P1") (pintype "bidirectional"))
    )
    (net (code "95") (name "unconnected-(USB-C-SBU1-PadA8)") (class "Default")
      (node (ref "USB-C") (pin "A8") (pinfunction "SBU1_A8") (pintype "bidirectional"))
    )
    (net (code "96") (name "unconnected-(USB-C-SBU2-PadB8)") (class "Default")
      (node (ref "USB-C") (pin "B8") (pinfunction "SBU2_B8") (pintype "bidirectional"))
    )
  )
)
